# 1-Schematic_ESP32_Development_Board.net
KiCad netlist of a schematic drawn in EasyEDA
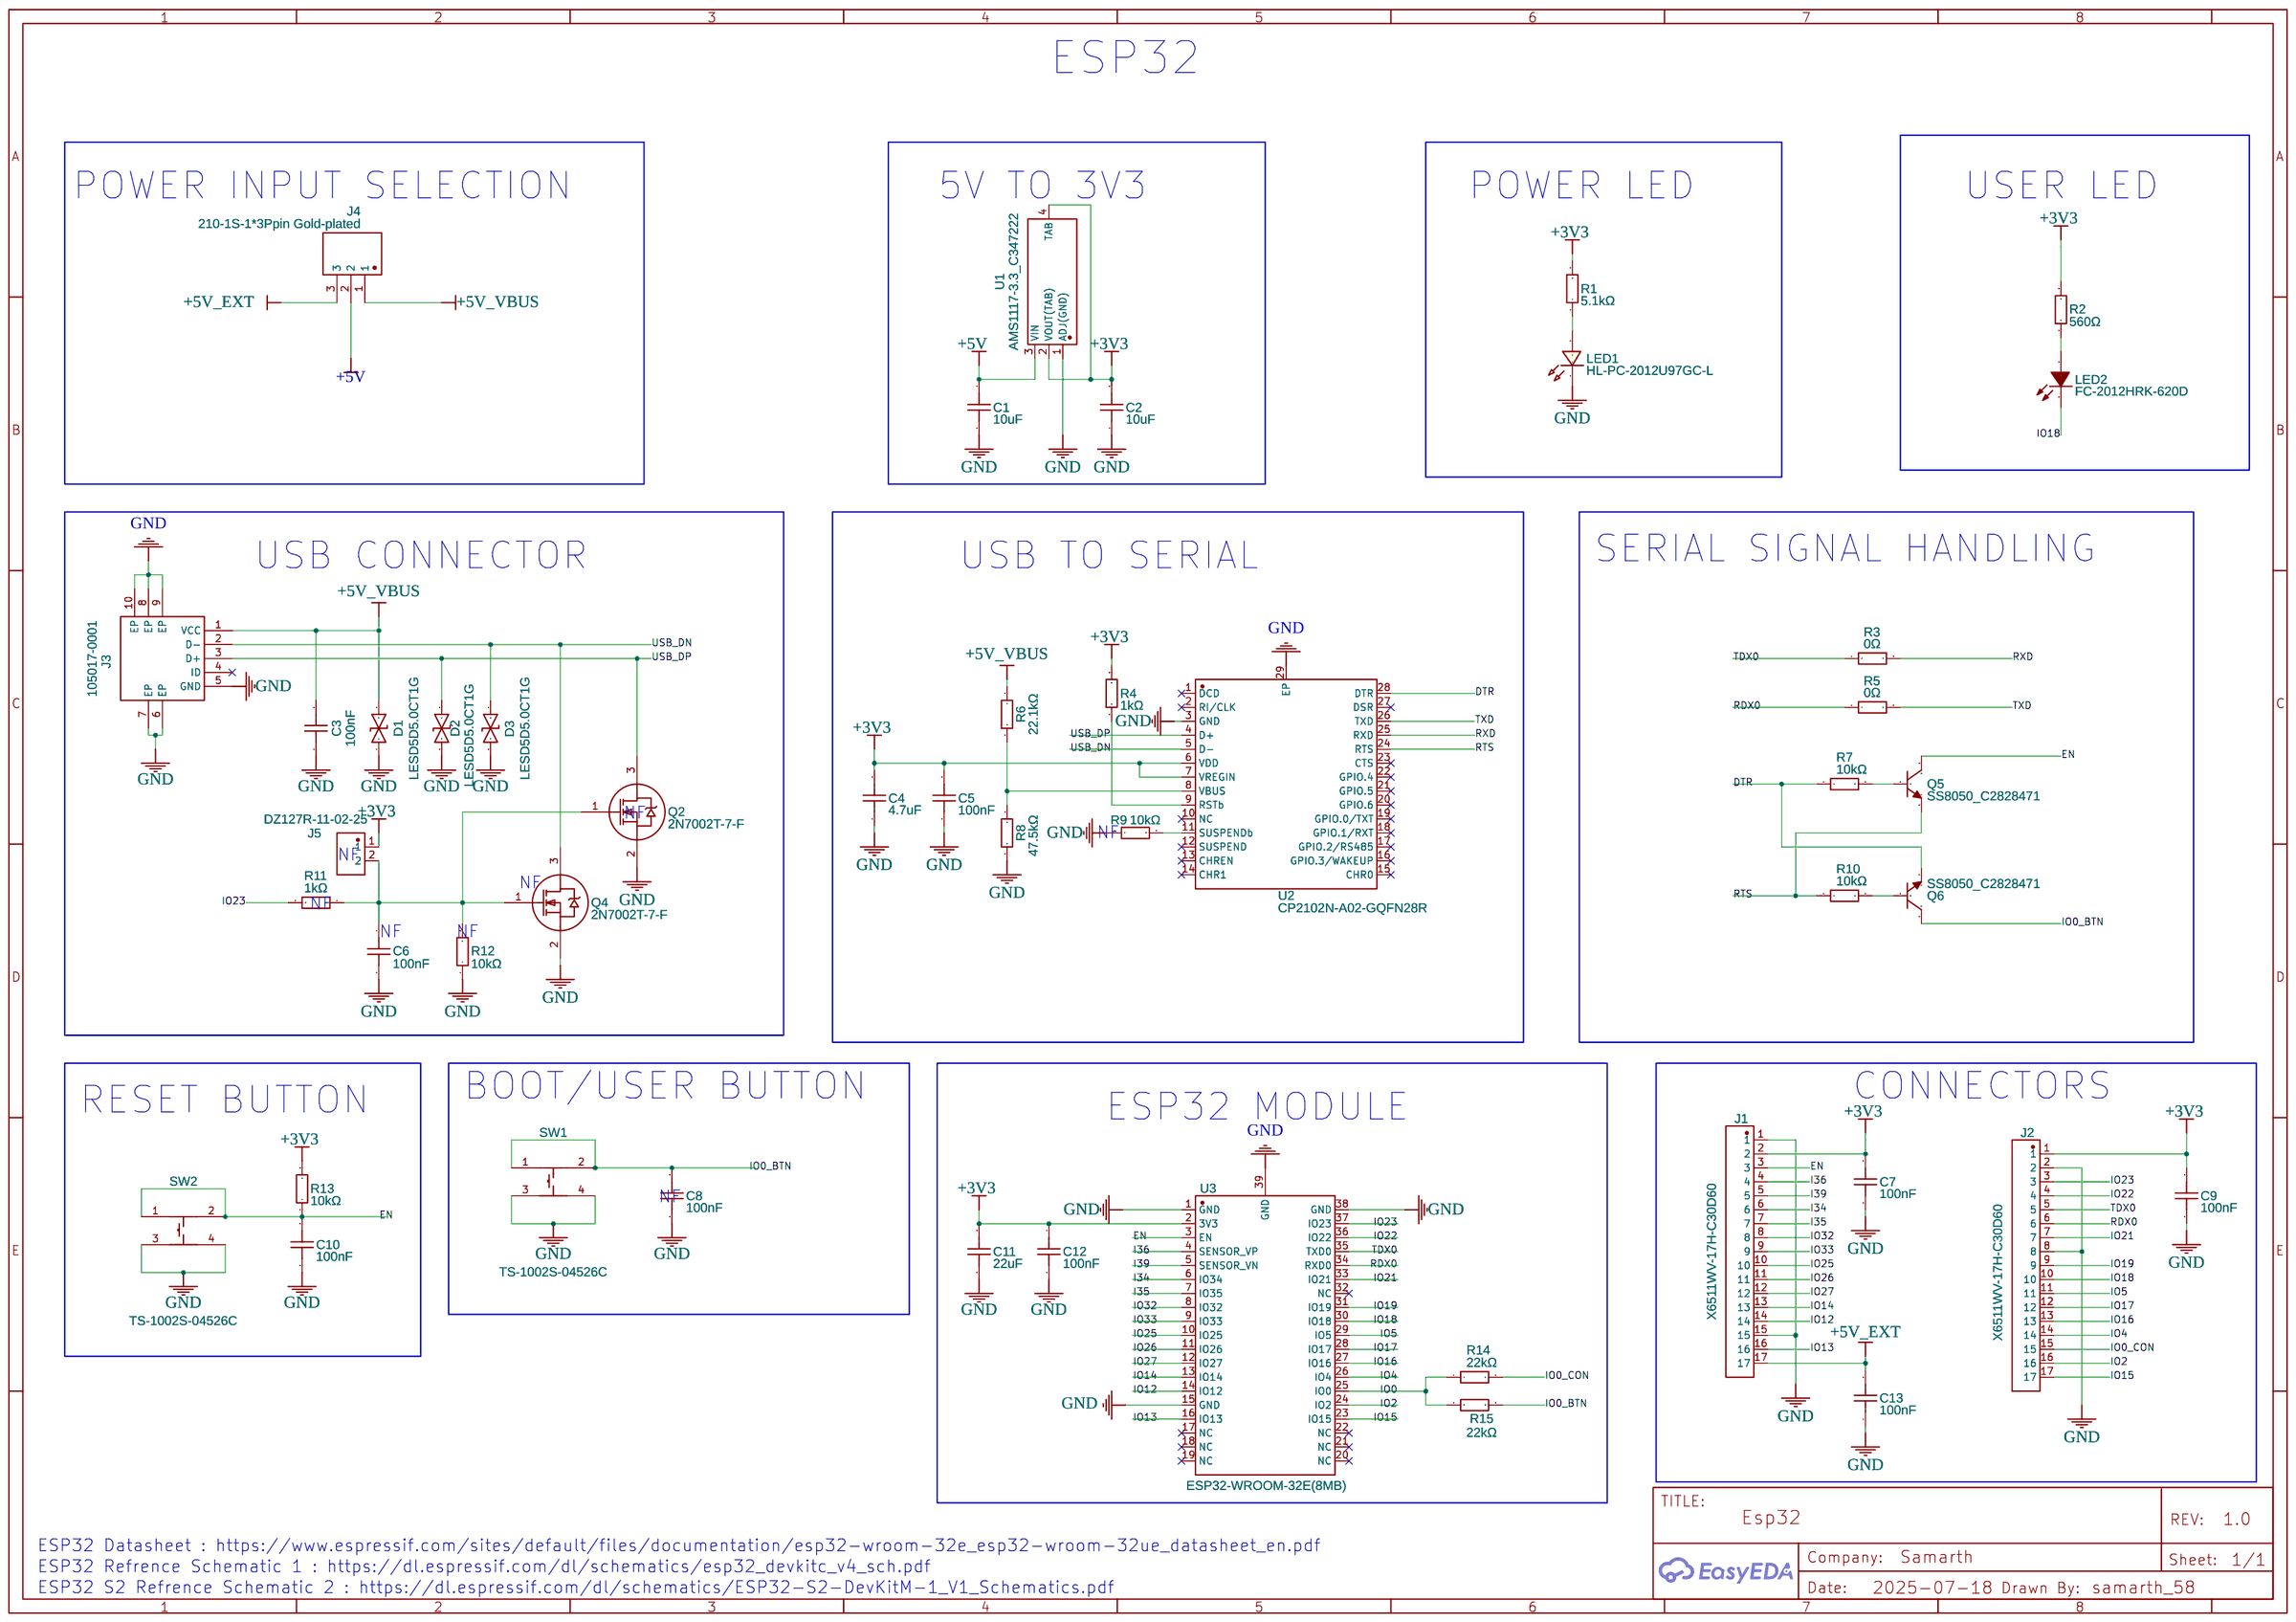
[diagram p0: schematic sheet]

(export (version "E")
  (design (tool "Eeschema 10.0.6"))
  (components
    (comp (ref "C1")
      (value "10uF")
      (fields
        (field (name "Manufacturer Part") "CL05A106MP5NUNC")
        (field (name "Manufacturer") "SAMSUNG(三星)")
      )
      (libsource (lib "") (part "CL05A106MP5NUNC_C315248"))
    )
    (comp (ref "C2")
      (value "10uF")
      (fields
        (field (name "Manufacturer Part") "CL05A106MP5NUNC")
        (field (name "Manufacturer") "SAMSUNG(三星)")
      )
      (libsource (lib "") (part "CL05A106MP5NUNC_C315248"))
    )
    (comp (ref "C3")
      (value "100nF")
      (fields
        (field (name "Manufacturer Part") "CL05B104KO5NNNC")
        (field (name "Manufacturer") "SAMSUNG(三星)")
      )
      (libsource (lib "") (part "CL05B104KO5NNNC_1"))
    )
    (comp (ref "C4")
      (value "4.7uF")
      (fields
        (field (name "Manufacturer Part") "CL05A475KP5NRNC")
        (field (name "Manufacturer") "SAMSUNG(三星)")
      )
      (libsource (lib "") (part "CL05A475KP5NRNC"))
    )
    (comp (ref "C5")
      (value "100nF")
      (fields
        (field (name "Manufacturer Part") "CL05B104KO5NNNC")
        (field (name "Manufacturer") "SAMSUNG(三星)")
      )
      (libsource (lib "") (part "CL05B104KO5NNNC_1"))
    )
    (comp (ref "C6")
      (value "100nF")
      (fields
        (field (name "Manufacturer Part") "CL05B104KO5NNNC")
        (field (name "Manufacturer") "SAMSUNG(三星)")
      )
      (libsource (lib "") (part "CL05B104KO5NNNC"))
    )
    (comp (ref "C7")
      (value "100nF")
      (fields
        (field (name "Manufacturer Part") "CL05B104KO5NNNC")
        (field (name "Manufacturer") "SAMSUNG(三星)")
      )
      (libsource (lib "") (part "CL05B104KO5NNNC_1"))
    )
    (comp (ref "C8")
      (value "100nF")
      (fields
        (field (name "Manufacturer Part") "CL05B104KO5NNNC")
        (field (name "Manufacturer") "SAMSUNG(三星)")
      )
      (libsource (lib "") (part "CL05B104KO5NNNC_1"))
    )
    (comp (ref "C9")
      (value "100nF")
      (fields
        (field (name "Manufacturer Part") "CL05B104KO5NNNC")
        (field (name "Manufacturer") "SAMSUNG(三星)")
      )
      (libsource (lib "") (part "CL05B104KO5NNNC_1"))
    )
    (comp (ref "C10")
      (value "100nF")
      (fields
        (field (name "Manufacturer Part") "CL05B104KO5NNNC")
        (field (name "Manufacturer") "SAMSUNG(三星)")
      )
      (libsource (lib "") (part "CL05B104KO5NNNC_1"))
    )
    (comp (ref "C11")
      (value "22uF")
      (fields
        (field (name "Manufacturer Part") "CL21A226MAYNNNE")
        (field (name "Manufacturer") "SAMSUNG(三星)")
      )
      (libsource (lib "") (part "CL21A226MAYNNNE"))
    )
    (comp (ref "C12")
      (value "100nF")
      (fields
        (field (name "Manufacturer Part") "CL05B104KO5NNNC")
        (field (name "Manufacturer") "SAMSUNG(三星)")
      )
      (libsource (lib "") (part "CL05B104KO5NNNC_1"))
    )
    (comp (ref "C13")
      (value "100nF")
      (fields
        (field (name "Manufacturer Part") "CL05B104KO5NNNC")
        (field (name "Manufacturer") "SAMSUNG(三星)")
      )
      (libsource (lib "") (part "CL05B104KO5NNNC_1"))
    )
    (comp (ref "D1")
      (value "LESD5D5.0CT1G")
      (fields (field (name "Manufacturer") "LRC(乐山无线电)"))
      (libsource (lib "") (part "LESD5D5.0CT1G"))
    )
    (comp (ref "D2")
      (value "LESD5D5.0CT1G")
      (fields (field (name "Manufacturer") "LRC(乐山无线电)"))
      (libsource (lib "") (part "LESD5D5.0CT1G_1"))
    )
    (comp (ref "D3")
      (value "LESD5D5.0CT1G")
      (fields (field (name "Manufacturer") "LRC(乐山无线电)"))
      (libsource (lib "") (part "LESD5D5.0CT1G_1"))
    )
    (comp (ref "J1")
      (value "X6511WV-17H-C30D60")
      (fields
        (field (name "Manufacturer Part") "X6511WV-17H-C60D30")
        (field (name "Manufacturer") "XKB Connection(中国星坤)")
      )
      (libsource (lib "") (part "X6511WV-17H-C30D60"))
    )
    (comp (ref "J2")
      (value "X6511WV-17H-C30D60")
      (fields
        (field (name "Manufacturer Part") "X6511WV-17H-C60D30")
        (field (name "Manufacturer") "XKB Connection(中国星坤)")
      )
      (libsource (lib "") (part "X6511WV-17H-C30D60"))
    )
    (comp (ref "J3")
      (value "105017-0001")
      (fields (field (name "Manufacturer Part") "1050170001") (field (name "Manufacturer") "MOLEX"))
      (libsource (lib "") (part "105017-0001"))
    )
    (comp (ref "J4")
      (value "210-1S-1*3Ppin Gold-plated")
      (fields (field (name "Manufacturer Part") "B-2101S03P-A110") (field (name "Manufacturer") "Ckmtw(灿科盟)"))
      (libsource (lib "") (part "210-1S-1*3Ppin Gold-plated"))
    )
    (comp (ref "J5")
      (value "DZ127R-11-02-25")
      (fields (field (name "Manufacturer") "DEALON(德艺隆)"))
      (libsource (lib "") (part "DZ127R-11-02-25"))
    )
    (comp (ref "LED1")
      (value "HL-PC-2012U97GC-L")
      (fields (field (name "Manufacturer") "HONGLITRONIC(鸿利光电)"))
      (libsource (lib "") (part "HL-PC-2012U97GC-L"))
    )
    (comp (ref "LED2")
      (value "FC-2012HRK-620D")
      (fields (field (name "Manufacturer Part") "NCD0805R1") (field (name "Manufacturer") "国星光电"))
      (libsource (lib "") (part "FC-2012HRK-620D"))
    )
    (comp (ref "Q2")
      (value "2N7002T-7-F")
      (fields (field (name "Manufacturer") "DIODES(美台)"))
      (libsource (lib "") (part "2N7002T-7-F"))
    )
    (comp (ref "Q4")
      (value "2N7002T-7-F")
      (fields (field (name "Manufacturer") "DIODES(美台)"))
      (libsource (lib "") (part "2N7002T-7-F"))
    )
    (comp (ref "Q5")
      (value "SS8050_C2828471")
      (fields (field (name "Manufacturer Part") "SS8050") (field (name "Manufacturer") "CBI(创基)"))
      (libsource (lib "") (part "SS8050_C2828471"))
    )
    (comp (ref "Q6")
      (value "SS8050_C2828471")
      (fields (field (name "Manufacturer Part") "SS8050") (field (name "Manufacturer") "CBI(创基)"))
      (libsource (lib "") (part "SS8050_C2828471_1"))
    )
    (comp (ref "R1")
      (value "5.1kΩ")
      (fields
        (field (name "Manufacturer Part") "0402WGF5101TCE")
        (field (name "Manufacturer") "UNI-ROYAL(厚声)")
      )
      (libsource (lib "") (part "0402WGF5101TCE"))
    )
    (comp (ref "R2")
      (value "560Ω")
      (fields
        (field (name "Manufacturer Part") "0402WGF5600TCE")
        (field (name "Manufacturer") "UNI-ROYAL(厚声)")
      )
      (libsource (lib "") (part "0402WGF5600TCE"))
    )
    (comp (ref "R3")
      (value "0Ω")
      (fields
        (field (name "Manufacturer Part") "0402WGF0000TCE")
        (field (name "Manufacturer") "UNI-ROYAL(厚声)")
      )
      (libsource (lib "") (part "0402WGF0000TCE"))
    )
    (comp (ref "R4")
      (value "1kΩ")
      (fields
        (field (name "Manufacturer Part") "0402WGF1001TCE")
        (field (name "Manufacturer") "UNI-ROYAL(厚声)")
      )
      (libsource (lib "") (part "0402WGF1001TCE"))
    )
    (comp (ref "R5")
      (value "0Ω")
      (fields
        (field (name "Manufacturer Part") "0402WGF0000TCE")
        (field (name "Manufacturer") "UNI-ROYAL(厚声)")
      )
      (libsource (lib "") (part "0402WGF0000TCE"))
    )
    (comp (ref "R6")
      (value "22.1kΩ")
      (fields
        (field (name "Manufacturer Part") "0402WGF2212TCE")
        (field (name "Manufacturer") "UNI-ROYAL(厚声)")
      )
      (libsource (lib "") (part "0402WGF2212TCE"))
    )
    (comp (ref "R7")
      (value "10kΩ")
      (fields
        (field (name "Manufacturer Part") "0402WGF1002TCE")
        (field (name "Manufacturer") "UNI-ROYAL(厚声)")
      )
      (libsource (lib "") (part "0402WGF1002TCE"))
    )
    (comp (ref "R8")
      (value "47.5kΩ")
      (fields
        (field (name "Manufacturer Part") "0402WGF4752TCE")
        (field (name "Manufacturer") "UNI-ROYAL(厚声)")
      )
      (libsource (lib "") (part "0402WGF4752TCE"))
    )
    (comp (ref "R9")
      (value "10kΩ")
      (fields
        (field (name "Manufacturer Part") "0402WGF1002TCE")
        (field (name "Manufacturer") "UNI-ROYAL(厚声)")
      )
      (libsource (lib "") (part "0402WGF1002TCE"))
    )
    (comp (ref "R10")
      (value "10kΩ")
      (fields
        (field (name "Manufacturer Part") "0402WGF1002TCE")
        (field (name "Manufacturer") "UNI-ROYAL(厚声)")
      )
      (libsource (lib "") (part "0402WGF1002TCE"))
    )
    (comp (ref "R11")
      (value "1kΩ")
      (fields
        (field (name "Manufacturer Part") "0402WGF1001TCE")
        (field (name "Manufacturer") "UNI-ROYAL(厚声)")
      )
      (libsource (lib "") (part "0402WGF1001TCE_1"))
    )
    (comp (ref "R12")
      (value "10kΩ")
      (fields
        (field (name "Manufacturer Part") "0402WGF1002TCE")
        (field (name "Manufacturer") "UNI-ROYAL(厚声)")
      )
      (libsource (lib "") (part "0402WGF1002TCE_1"))
    )
    (comp (ref "R13")
      (value "10kΩ")
      (fields
        (field (name "Manufacturer Part") "0402WGF1002TCE")
        (field (name "Manufacturer") "UNI-ROYAL(厚声)")
      )
      (libsource (lib "") (part "0402WGF1002TCE_1"))
    )
    (comp (ref "R14")
      (value "22kΩ")
      (fields
        (field (name "Manufacturer Part") "0402WGF2202TCE")
        (field (name "Manufacturer") "UNI-ROYAL(厚声)")
      )
      (libsource (lib "") (part "0402WGF2202TCE"))
    )
    (comp (ref "R15")
      (value "22kΩ")
      (fields
        (field (name "Manufacturer Part") "0402WGF2202TCE")
        (field (name "Manufacturer") "UNI-ROYAL(厚声)")
      )
      (libsource (lib "") (part "0402WGF2202TCE"))
    )
    (comp (ref "SW1")
      (value "TS-1002S-04526C")
      (fields (field (name "Manufacturer") "XUNPU(讯普)"))
      (libsource (lib "") (part "TS-1002S-04526C"))
    )
    (comp (ref "SW2")
      (value "TS-1002S-04526C")
      (fields (field (name "Manufacturer") "XUNPU(讯普)"))
      (libsource (lib "") (part "TS-1002S-04526C"))
    )
    (comp (ref "U1")
      (value "AMS1117-3.3_C347222")
      (fields (field (name "Manufacturer Part") "AMS1117-3.3") (field (name "Manufacturer") "UMW(友台半导体)"))
      (libsource (lib "") (part "AMS1117-3.3_C347222"))
    )
    (comp (ref "U2")
      (value "CP2102N-A02-GQFN28R")
      (fields (field (name "Manufacturer") "SKYWORKS/SILICON LABS(芯科)"))
      (libsource (lib "") (part "CP2102N-A02-GQFN28R"))
    )
    (comp (ref "U3")
      (value "ESP32-WROOM-32E(8MB)")
      (fields
        (field (name "Manufacturer Part") "ESP32-WROOM-32E-N8")
        (field (name "Manufacturer") "ESPRESSIF(乐鑫)")
      )
      (libsource (lib "") (part "ESP32-WROOM-32E(8MB)"))
    )
  )
  (nets
    (net (code "1") (name "+3V3") (class "Default")
      (node (ref "C11") (pin "2") (pinfunction "2_2") (pintype "unspecified"))
      (node (ref "C12") (pin "2") (pinfunction "2_2") (pintype "unspecified"))
      (node (ref "C2") (pin "2") (pinfunction "2_2") (pintype "unspecified"))
      (node (ref "C4") (pin "2") (pinfunction "2_2") (pintype "unspecified"))
      (node (ref "C5") (pin "2") (pinfunction "2_2") (pintype "unspecified"))
      (node (ref "C7") (pin "2") (pinfunction "2_2") (pintype "unspecified"))
      (node (ref "C9") (pin "2") (pinfunction "2_2") (pintype "unspecified"))
      (node (ref "J1") (pin "2") (pinfunction "2_2") (pintype "unspecified"))
      (node (ref "J2") (pin "1") (pinfunction "1_1") (pintype "unspecified"))
      (node (ref "J5") (pin "1") (pinfunction "1_1") (pintype "unspecified"))
      (node (ref "R1") (pin "2") (pinfunction "2_2") (pintype "input"))
      (node (ref "R13") (pin "2") (pinfunction "2_2") (pintype "input"))
      (node (ref "R2") (pin "2") (pinfunction "2_2") (pintype "input"))
      (node (ref "R4") (pin "2") (pinfunction "2_2") (pintype "input"))
      (node (ref "U1") (pin "2") (pinfunction "VOUT(TAB)_2") (pintype "unspecified"))
      (node (ref "U1") (pin "4") (pinfunction "TAB_4") (pintype "unspecified"))
      (node (ref "U2") (pin "6") (pinfunction "VDD_6") (pintype "unspecified"))
      (node (ref "U2") (pin "7") (pinfunction "VREGIN_7") (pintype "unspecified"))
      (node (ref "U3") (pin "2") (pinfunction "3V3_2") (pintype "unspecified"))
    )
    (net (code "2") (name "+5V") (class "Default")
      (node (ref "C1") (pin "2") (pinfunction "2_2") (pintype "unspecified"))
      (node (ref "J4") (pin "2") (pinfunction "2_2") (pintype "unspecified"))
      (node (ref "U1") (pin "3") (pinfunction "VIN_3") (pintype "unspecified"))
    )
    (net (code "3") (name "+5V_EXT") (class "Default")
      (node (ref "C13") (pin "2") (pinfunction "2_2") (pintype "unspecified"))
      (node (ref "J1") (pin "17") (pinfunction "17_17") (pintype "unspecified"))
      (node (ref "J4") (pin "3") (pinfunction "3_3") (pintype "unspecified"))
    )
    (net (code "4") (name "+5V_VBUS") (class "Default")
      (node (ref "C3") (pin "2") (pinfunction "2_2") (pintype "unspecified"))
      (node (ref "D1") (pin "2") (pinfunction "2_2") (pintype "unspecified"))
      (node (ref "J3") (pin "1") (pinfunction "VCC_1") (pintype "unspecified"))
      (node (ref "J4") (pin "1") (pinfunction "1_1") (pintype "unspecified"))
      (node (ref "R6") (pin "2") (pinfunction "2_2") (pintype "input"))
    )
    (net (code "5") (name "/DTR") (class "Default")
      (node (ref "Q6") (pin "2") (pinfunction "E_2") (pintype "input"))
      (node (ref "R7") (pin "1") (pinfunction "1_1") (pintype "input"))
      (node (ref "U2") (pin "28") (pinfunction "DTR_28") (pintype "unspecified"))
    )
    (net (code "6") (name "/EN") (class "Default")
      (node (ref "C10") (pin "2") (pinfunction "2_2") (pintype "unspecified"))
      (node (ref "J1") (pin "3") (pinfunction "3_3") (pintype "unspecified"))
      (node (ref "Q5") (pin "3") (pinfunction "C_3") (pintype "input"))
      (node (ref "R13") (pin "1") (pinfunction "1_1") (pintype "input"))
      (node (ref "SW2") (pin "1") (pinfunction "1_1") (pintype "unspecified"))
      (node (ref "SW2") (pin "2") (pinfunction "2_2") (pintype "unspecified"))
      (node (ref "U3") (pin "3") (pinfunction "EN_3") (pintype "unspecified"))
    )
    (net (code "7") (name "/I34") (class "Default")
      (node (ref "J1") (pin "6") (pinfunction "6_6") (pintype "unspecified"))
      (node (ref "U3") (pin "6") (pinfunction "IO34_6") (pintype "unspecified"))
    )
    (net (code "8") (name "/I35") (class "Default")
      (node (ref "J1") (pin "7") (pinfunction "7_7") (pintype "unspecified"))
      (node (ref "U3") (pin "7") (pinfunction "IO35_7") (pintype "unspecified"))
    )
    (net (code "9") (name "/I36") (class "Default")
      (node (ref "J1") (pin "4") (pinfunction "4_4") (pintype "unspecified"))
      (node (ref "U3") (pin "4") (pinfunction "SENSOR_VP_4") (pintype "unspecified"))
    )
    (net (code "10") (name "/I39") (class "Default")
      (node (ref "J1") (pin "5") (pinfunction "5_5") (pintype "unspecified"))
      (node (ref "U3") (pin "5") (pinfunction "SENSOR_VN_5") (pintype "unspecified"))
    )
    (net (code "11") (name "/IO0") (class "Default")
      (node (ref "R14") (pin "1") (pinfunction "1_1") (pintype "input"))
      (node (ref "R15") (pin "1") (pinfunction "1_1") (pintype "input"))
      (node (ref "U3") (pin "25") (pinfunction "IO0_25") (pintype "unspecified"))
    )
    (net (code "12") (name "/IO0_BTN") (class "Default")
      (node (ref "C8") (pin "2") (pinfunction "2_2") (pintype "unspecified"))
      (node (ref "Q6") (pin "3") (pinfunction "C_3") (pintype "input"))
      (node (ref "R15") (pin "2") (pinfunction "2_2") (pintype "input"))
      (node (ref "SW1") (pin "1") (pinfunction "1_1") (pintype "unspecified"))
      (node (ref "SW1") (pin "2") (pinfunction "2_2") (pintype "unspecified"))
    )
    (net (code "13") (name "/IO0_CON") (class "Default")
      (node (ref "J2") (pin "15") (pinfunction "15_15") (pintype "unspecified"))
      (node (ref "R14") (pin "2") (pinfunction "2_2") (pintype "input"))
    )
    (net (code "14") (name "/IO2") (class "Default")
      (node (ref "J2") (pin "16") (pinfunction "16_16") (pintype "unspecified"))
      (node (ref "U3") (pin "24") (pinfunction "IO2_24") (pintype "unspecified"))
    )
    (net (code "15") (name "/IO4") (class "Default")
      (node (ref "J2") (pin "14") (pinfunction "14_14") (pintype "unspecified"))
      (node (ref "U3") (pin "26") (pinfunction "IO4_26") (pintype "unspecified"))
    )
    (net (code "16") (name "/IO5") (class "Default")
      (node (ref "J2") (pin "11") (pinfunction "11_11") (pintype "unspecified"))
      (node (ref "U3") (pin "29") (pinfunction "IO5_29") (pintype "unspecified"))
    )
    (net (code "17") (name "/IO12") (class "Default")
      (node (ref "J1") (pin "14") (pinfunction "14_14") (pintype "unspecified"))
      (node (ref "U3") (pin "14") (pinfunction "IO12_14") (pintype "unspecified"))
    )
    (net (code "18") (name "/IO13") (class "Default")
      (node (ref "J1") (pin "16") (pinfunction "16_16") (pintype "unspecified"))
      (node (ref "U3") (pin "16") (pinfunction "IO13_16") (pintype "unspecified"))
    )
    (net (code "19") (name "/IO14") (class "Default")
      (node (ref "J1") (pin "13") (pinfunction "13_13") (pintype "unspecified"))
      (node (ref "U3") (pin "13") (pinfunction "IO14_13") (pintype "unspecified"))
    )
    (net (code "20") (name "/IO15") (class "Default")
      (node (ref "J2") (pin "17") (pinfunction "17_17") (pintype "unspecified"))
      (node (ref "U3") (pin "23") (pinfunction "IO15_23") (pintype "unspecified"))
    )
    (net (code "21") (name "/IO16") (class "Default")
      (node (ref "J2") (pin "13") (pinfunction "13_13") (pintype "unspecified"))
      (node (ref "U3") (pin "27") (pinfunction "IO16_27") (pintype "unspecified"))
    )
    (net (code "22") (name "/IO17") (class "Default")
      (node (ref "J2") (pin "12") (pinfunction "12_12") (pintype "unspecified"))
      (node (ref "U3") (pin "28") (pinfunction "IO17_28") (pintype "unspecified"))
    )
    (net (code "23") (name "/IO18") (class "Default")
      (node (ref "J2") (pin "10") (pinfunction "10_10") (pintype "unspecified"))
      (node (ref "LED2") (pin "2") (pinfunction "-_2") (pintype "unspecified"))
      (node (ref "U3") (pin "30") (pinfunction "IO18_30") (pintype "unspecified"))
    )
    (net (code "24") (name "/IO19") (class "Default")
      (node (ref "J2") (pin "9") (pinfunction "9_9") (pintype "unspecified"))
      (node (ref "U3") (pin "31") (pinfunction "IO19_31") (pintype "unspecified"))
    )
    (net (code "25") (name "/IO21") (class "Default")
      (node (ref "J2") (pin "7") (pinfunction "7_7") (pintype "unspecified"))
      (node (ref "U3") (pin "33") (pinfunction "IO21_33") (pintype "unspecified"))
    )
    (net (code "26") (name "/IO22") (class "Default")
      (node (ref "J2") (pin "4") (pinfunction "4_4") (pintype "unspecified"))
      (node (ref "U3") (pin "36") (pinfunction "IO22_36") (pintype "unspecified"))
    )
    (net (code "27") (name "/IO23") (class "Default")
      (node (ref "J2") (pin "3") (pinfunction "3_3") (pintype "unspecified"))
      (node (ref "R11") (pin "2") (pinfunction "2_2") (pintype "input"))
      (node (ref "U3") (pin "37") (pinfunction "IO23_37") (pintype "unspecified"))
    )
    (net (code "28") (name "/IO25") (class "Default")
      (node (ref "J1") (pin "10") (pinfunction "10_10") (pintype "unspecified"))
      (node (ref "U3") (pin "10") (pinfunction "IO25_10") (pintype "unspecified"))
    )
    (net (code "29") (name "/IO26") (class "Default")
      (node (ref "J1") (pin "11") (pinfunction "11_11") (pintype "unspecified"))
      (node (ref "U3") (pin "11") (pinfunction "IO26_11") (pintype "unspecified"))
    )
    (net (code "30") (name "/IO27") (class "Default")
      (node (ref "J1") (pin "12") (pinfunction "12_12") (pintype "unspecified"))
      (node (ref "U3") (pin "12") (pinfunction "IO27_12") (pintype "unspecified"))
    )
    (net (code "31") (name "/IO32") (class "Default")
      (node (ref "J1") (pin "8") (pinfunction "8_8") (pintype "unspecified"))
      (node (ref "U3") (pin "8") (pinfunction "IO32_8") (pintype "unspecified"))
    )
    (net (code "32") (name "/IO33") (class "Default")
      (node (ref "J1") (pin "9") (pinfunction "9_9") (pintype "unspecified"))
      (node (ref "U3") (pin "9") (pinfunction "IO33_9") (pintype "unspecified"))
    )
    (net (code "33") (name "/RDX0") (class "Default")
      (node (ref "J2") (pin "6") (pinfunction "6_6") (pintype "unspecified"))
      (node (ref "R5") (pin "1") (pinfunction "1_1") (pintype "input"))
      (node (ref "U3") (pin "34") (pinfunction "RXD0_34") (pintype "unspecified"))
    )
    (net (code "34") (name "/RTS") (class "Default")
      (node (ref "Q5") (pin "2") (pinfunction "E_2") (pintype "input"))
      (node (ref "R10") (pin "1") (pinfunction "1_1") (pintype "input"))
      (node (ref "U2") (pin "24") (pinfunction "RTS_24") (pintype "unspecified"))
    )
    (net (code "35") (name "/RXD") (class "Default")
      (node (ref "R3") (pin "2") (pinfunction "2_2") (pintype "input"))
      (node (ref "U2") (pin "25") (pinfunction "RXD_25") (pintype "unspecified"))
    )
    (net (code "36") (name "/TDX0") (class "Default")
      (node (ref "J2") (pin "5") (pinfunction "5_5") (pintype "unspecified"))
      (node (ref "R3") (pin "1") (pinfunction "1_1") (pintype "input"))
      (node (ref "U3") (pin "35") (pinfunction "TXD0_35") (pintype "unspecified"))
    )
    (net (code "37") (name "/TXD") (class "Default")
      (node (ref "R5") (pin "2") (pinfunction "2_2") (pintype "input"))
      (node (ref "U2") (pin "26") (pinfunction "TXD_26") (pintype "unspecified"))
    )
    (net (code "38") (name "/USB_DN") (class "Default")
      (node (ref "D3") (pin "1") (pinfunction "1_1") (pintype "unspecified"))
      (node (ref "J3") (pin "2") (pinfunction "D-_2") (pintype "unspecified"))
      (node (ref "Q4") (pin "3") (pinfunction "D_3") (pintype "unspecified"))
      (node (ref "U2") (pin "5") (pinfunction "D-_5") (pintype "unspecified"))
    )
    (net (code "39") (name "/USB_DP") (class "Default")
      (node (ref "D2") (pin "1") (pinfunction "1_1") (pintype "unspecified"))
      (node (ref "J3") (pin "3") (pinfunction "D+_3") (pintype "unspecified"))
      (node (ref "Q2") (pin "3") (pinfunction "D_3") (pintype "unspecified"))
      (node (ref "U2") (pin "4") (pinfunction "D+_4") (pintype "unspecified"))
    )
    (net (code "40") (name "GND") (class "Default")
      (node (ref "C1") (pin "1") (pinfunction "1_1") (pintype "unspecified"))
      (node (ref "C10") (pin "1") (pinfunction "1_1") (pintype "unspecified"))
      (node (ref "C11") (pin "1") (pinfunction "1_1") (pintype "unspecified"))
      (node (ref "C12") (pin "1") (pinfunction "1_1") (pintype "unspecified"))
      (node (ref "C13") (pin "1") (pinfunction "1_1") (pintype "unspecified"))
      (node (ref "C2") (pin "1") (pinfunction "1_1") (pintype "unspecified"))
      (node (ref "C3") (pin "1") (pinfunction "1_1") (pintype "unspecified"))
      (node (ref "C4") (pin "1") (pinfunction "1_1") (pintype "unspecified"))
      (node (ref "C5") (pin "1") (pinfunction "1_1") (pintype "unspecified"))
      (node (ref "C6") (pin "2") (pinfunction "2_2") (pintype "unspecified"))
      (node (ref "C7") (pin "1") (pinfunction "1_1") (pintype "unspecified"))
      (node (ref "C8") (pin "1") (pinfunction "1_1") (pintype "unspecified"))
      (node (ref "C9") (pin "1") (pinfunction "1_1") (pintype "unspecified"))
      (node (ref "D1") (pin "1") (pinfunction "1_1") (pintype "unspecified"))
      (node (ref "D2") (pin "2") (pinfunction "2_2") (pintype "unspecified"))
      (node (ref "D3") (pin "2") (pinfunction "2_2") (pintype "unspecified"))
      (node (ref "J1") (pin "1") (pinfunction "1_1") (pintype "unspecified"))
      (node (ref "J1") (pin "15") (pinfunction "15_15") (pintype "unspecified"))
      (node (ref "J2") (pin "2") (pinfunction "2_2") (pintype "unspecified"))
      (node (ref "J2") (pin "8") (pinfunction "8_8") (pintype "unspecified"))
      (node (ref "J3") (pin "10") (pinfunction "EP_10") (pintype "unspecified"))
      (node (ref "J3") (pin "5") (pinfunction "GND_5") (pintype "unspecified"))
      (node (ref "J3") (pin "6") (pinfunction "EP_6") (pintype "unspecified"))
      (node (ref "J3") (pin "7") (pinfunction "EP_7") (pintype "unspecified"))
      (node (ref "J3") (pin "8") (pinfunction "EP_8") (pintype "unspecified"))
      (node (ref "J3") (pin "9") (pinfunction "EP_9") (pintype "unspecified"))
      (node (ref "LED1") (pin "1") (pinfunction "-_1") (pintype "unspecified"))
      (node (ref "Q2") (pin "2") (pinfunction "S_2") (pintype "unspecified"))
      (node (ref "Q4") (pin "2") (pinfunction "S_2") (pintype "unspecified"))
      (node (ref "R12") (pin "1") (pinfunction "1_1") (pintype "input"))
      (node (ref "R8") (pin "1") (pinfunction "1_1") (pintype "input"))
      (node (ref "R9") (pin "1") (pinfunction "1_1") (pintype "input"))
      (node (ref "SW1") (pin "3") (pinfunction "3_3") (pintype "unspecified"))
      (node (ref "SW1") (pin "4") (pinfunction "4_4") (pintype "unspecified"))
      (node (ref "SW2") (pin "3") (pinfunction "3_3") (pintype "unspecified"))
      (node (ref "SW2") (pin "4") (pinfunction "4_4") (pintype "unspecified"))
      (node (ref "U1") (pin "1") (pinfunction "ADJ(GND)_1") (pintype "unspecified"))
      (node (ref "U2") (pin "29") (pinfunction "EP_29") (pintype "unspecified"))
      (node (ref "U2") (pin "3") (pinfunction "GND_3") (pintype "unspecified"))
      (node (ref "U3") (pin "1") (pinfunction "GND_1") (pintype "unspecified"))
      (node (ref "U3") (pin "15") (pinfunction "GND_15") (pintype "unspecified"))
      (node (ref "U3") (pin "38") (pinfunction "GND_38") (pintype "unspecified"))
      (node (ref "U3") (pin "39") (pinfunction "GND_39") (pintype "unspecified"))
    )
    (net (code "41") (name "Net-(LED1-+)") (class "Default")
      (node (ref "LED1") (pin "2") (pinfunction "+_2") (pintype "unspecified"))
      (node (ref "R1") (pin "1") (pinfunction "1_1") (pintype "input"))
    )
    (net (code "42") (name "Net-(LED2-+)") (class "Default")
      (node (ref "LED2") (pin "1") (pinfunction "+_1") (pintype "unspecified"))
      (node (ref "R2") (pin "1") (pinfunction "1_1") (pintype "input"))
    )
    (net (code "43") (name "Net-(Q2-G)") (class "Default")
      (node (ref "C6") (pin "1") (pinfunction "1_1") (pintype "unspecified"))
      (node (ref "J5") (pin "2") (pinfunction "2_2") (pintype "unspecified"))
      (node (ref "Q2") (pin "1") (pinfunction "G_1") (pintype "unspecified"))
      (node (ref "Q4") (pin "1") (pinfunction "G_1") (pintype "unspecified"))
      (node (ref "R11") (pin "1") (pinfunction "1_1") (pintype "input"))
      (node (ref "R12") (pin "2") (pinfunction "2_2") (pintype "input"))
    )
    (net (code "44") (name "Net-(Q5-B)") (class "Default")
      (node (ref "Q5") (pin "1") (pinfunction "B_1") (pintype "input"))
      (node (ref "R7") (pin "2") (pinfunction "2_2") (pintype "input"))
    )
    (net (code "45") (name "Net-(Q6-B)") (class "Default")
      (node (ref "Q6") (pin "1") (pinfunction "B_1") (pintype "input"))
      (node (ref "R10") (pin "2") (pinfunction "2_2") (pintype "input"))
    )
    (net (code "46") (name "Net-(U2-RSTb)") (class "Default")
      (node (ref "R4") (pin "1") (pinfunction "1_1") (pintype "input"))
      (node (ref "U2") (pin "9") (pinfunction "RSTb_9") (pintype "unspecified"))
    )
    (net (code "47") (name "Net-(U2-SUSPENDb)") (class "Default")
      (node (ref "R9") (pin "2") (pinfunction "2_2") (pintype "input"))
      (node (ref "U2") (pin "11") (pinfunction "SUSPENDb_11") (pintype "unspecified"))
    )
    (net (code "48") (name "Net-(U2-VBUS)") (class "Default")
      (node (ref "R6") (pin "1") (pinfunction "1_1") (pintype "input"))
      (node (ref "R8") (pin "2") (pinfunction "2_2") (pintype "input"))
      (node (ref "U2") (pin "8") (pinfunction "VBUS_8") (pintype "unspecified"))
    )
    (net (code "49") (name "unconnected-(J3-ID-Pad4)") (class "Default")
      (node (ref "J3") (pin "4") (pinfunction "ID_4") (pintype "unspecified+no_connect"))
    )
    (net (code "50") (name "unconnected-(U2-CHR0-Pad15)") (class "Default")
      (node (ref "U2") (pin "15") (pinfunction "CHR0_15") (pintype "unspecified+no_connect"))
    )
    (net (code "51") (name "unconnected-(U2-CHR1-Pad14)") (class "Default")
      (node (ref "U2") (pin "14") (pinfunction "CHR1_14") (pintype "unspecified+no_connect"))
    )
    (net (code "52") (name "unconnected-(U2-CHREN-Pad13)") (class "Default")
      (node (ref "U2") (pin "13") (pinfunction "CHREN_13") (pintype "unspecified+no_connect"))
    )
    (net (code "53") (name "unconnected-(U2-CTS-Pad23)") (class "Default")
      (node (ref "U2") (pin "23") (pinfunction "CTS_23") (pintype "unspecified+no_connect"))
    )
    (net (code "54") (name "unconnected-(U2-DCD-Pad1)") (class "Default")
      (node (ref "U2") (pin "1") (pinfunction "DCD_1") (pintype "unspecified+no_connect"))
    )
    (net (code "55") (name "unconnected-(U2-DSR-Pad27)") (class "Default")
      (node (ref "U2") (pin "27") (pinfunction "DSR_27") (pintype "unspecified+no_connect"))
    )
    (net (code "56") (name "unconnected-(U2-GPIO.0{slash}TXT-Pad19)") (class "Default")
      (node (ref "U2") (pin "19") (pinfunction "GPIO.0/TXT_19") (pintype "unspecified+no_connect"))
    )
    (net (code "57") (name "unconnected-(U2-GPIO.1{slash}RXT-Pad18)") (class "Default")
      (node (ref "U2") (pin "18") (pinfunction "GPIO.1/RXT_18") (pintype "unspecified+no_connect"))
    )
    (net (code "58") (name "unconnected-(U2-GPIO.2{slash}RS485-Pad17)") (class "Default")
      (node (ref "U2") (pin "17") (pinfunction "GPIO.2/RS485_17") (pintype "unspecified+no_connect"))
    )
    (net (code "59") (name "unconnected-(U2-GPIO.3{slash}WAKEUP-Pad16)") (class "Default")
      (node (ref "U2") (pin "16") (pinfunction "GPIO.3/WAKEUP_16") (pintype "unspecified+no_connect"))
    )
    (net (code "60") (name "unconnected-(U2-GPIO.4-Pad22)") (class "Default")
      (node (ref "U2") (pin "22") (pinfunction "GPIO.4_22") (pintype "unspecified+no_connect"))
    )
    (net (code "61") (name "unconnected-(U2-GPIO.5-Pad21)") (class "Default")
      (node (ref "U2") (pin "21") (pinfunction "GPIO.5_21") (pintype "unspecified+no_connect"))
    )
    (net (code "62") (name "unconnected-(U2-GPIO.6-Pad20)") (class "Default")
      (node (ref "U2") (pin "20") (pinfunction "GPIO.6_20") (pintype "unspecified+no_connect"))
    )
    (net (code "63") (name "unconnected-(U2-NC-Pad10)") (class "Default")
      (node (ref "U2") (pin "10") (pinfunction "NC_10") (pintype "unspecified+no_connect"))
    )
    (net (code "64") (name "unconnected-(U2-RI{slash}CLK-Pad2)") (class "Default")
      (node (ref "U2") (pin "2") (pinfunction "RI/CLK_2") (pintype "unspecified+no_connect"))
    )
    (net (code "65") (name "unconnected-(U2-SUSPEND-Pad12)") (class "Default")
      (node (ref "U2") (pin "12") (pinfunction "SUSPEND_12") (pintype "unspecified+no_connect"))
    )
    (net (code "66") (name "unconnected-(U3-NC-Pad17)") (class "Default")
      (node (ref "U3") (pin "17") (pinfunction "NC_17") (pintype "unspecified+no_connect"))
    )
    (net (code "67") (name "unconnected-(U3-NC-Pad18)") (class "Default")
      (node (ref "U3") (pin "18") (pinfunction "NC_18") (pintype "unspecified+no_connect"))
    )
    (net (code "68") (name "unconnected-(U3-NC-Pad19)") (class "Default")
      (node (ref "U3") (pin "19") (pinfunction "NC_19") (pintype "unspecified+no_connect"))
    )
    (net (code "69") (name "unconnected-(U3-NC-Pad20)") (class "Default")
      (node (ref "U3") (pin "20") (pinfunction "NC_20") (pintype "unspecified+no_connect"))
    )
    (net (code "70") (name "unconnected-(U3-NC-Pad21)") (class "Default")
      (node (ref "U3") (pin "21") (pinfunction "NC_21") (pintype "unspecified+no_connect"))
    )
    (net (code "71") (name "unconnected-(U3-NC-Pad22)") (class "Default")
      (node (ref "U3") (pin "22") (pinfunction "NC_22") (pintype "unspecified+no_connect"))
    )
    (net (code "72") (name "unconnected-(U3-NC-Pad32)") (class "Default")
      (node (ref "U3") (pin "32") (pinfunction "NC_32") (pintype "unspecified+no_connect"))
    )
  )
)
